# MXChip.net
KiCad netlist of a schematic drawn in Altium Designer
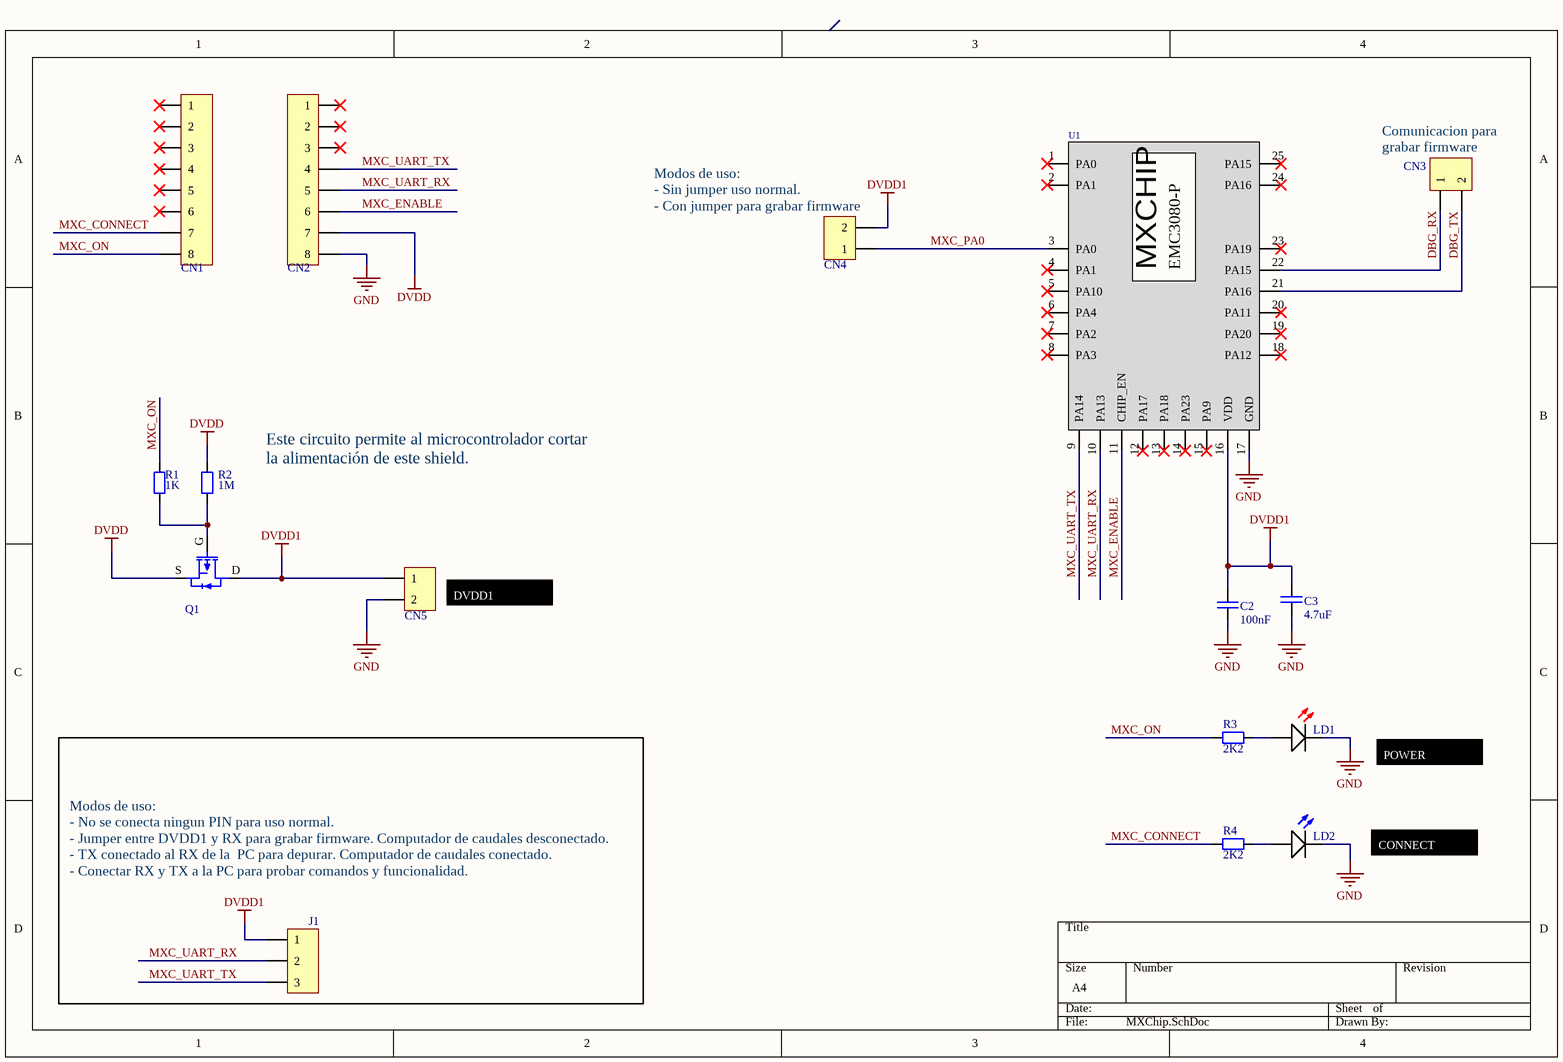
[diagram p0: MXChip.SchDoc]

(export (version "E")
  (design (tool "Eeschema 10.0.6"))
  (components
    (comp (ref "C2")
      (value "100nF")
      (footprint "CAP_SM0805_YAGEOCC2_N")
      (description "CAP 100nF SM0805 X7R 25V YAGEO CC2")
      (fields
        (field (name "MANUFACTURER") "Yageo")
        (field (name "MANUFACTURER PART NUMBER") "CC0805KRX7R8BB104")
      )
      (libsource (lib "Yageo") (part "CC0805KRX7R8BB104"))
    )
    (comp (ref "C3")
      (value "4.7uF")
      (footprint "CAP_SM0805_YAGEOCC2_N")
      (description "CAP 4.7uF SM0805 X5R 10V YAGEO CC2")
      (fields
        (field (name "MANUFACTURER") "Yageo")
        (field (name "MANUFACTURER PART NUMBER") "CC0805KRX5R6BB475")
      )
      (libsource (lib "Yageo") (part "CC0805KRX5R6BB475"))
    )
    (comp (ref "CN1")
      (value "DEALON DZ200R-11-08-39")
      (footprint "HEADER PIN 1X8 2mm")
      (description "1 x 8 - true hole  2mm - Pb free")
      (fields
        (field (name "MANUFACTURER") "Amphenol ICC")
        (field (name "MANUFACTURER PART NUMBER") "DZ200R-11-08-39")
      )
      (libsource (lib "header_pin") (part "DEALON DZ200R-11-08-39"))
    )
    (comp (ref "CN2")
      (value "DEALON DZ200R-11-08-39")
      (footprint "HEADER PIN 1X8 2mm")
      (description "1 x 8 - true hole  2mm - Pb free")
      (fields
        (field (name "MANUFACTURER") "Amphenol ICC")
        (field (name "MANUFACTURER PART NUMBER") "DZ200R-11-08-39")
      )
      (libsource (lib "") (part "DEALON DZ200R-11-08-39_1"))
    )
    (comp (ref "CN3")
      (value "Completar BOM con modelo 54101-T0600LF (o equivalente), es de 36 posiciones, este componente necesita cortar 2 por componente")
      (footprint "HEADER PIN 1X2")
      (description "1 x 2 - true hole  2.54mm - Pb free")
      (fields (field (name "MANUFACTURER") "Amphenol ICC"))
      (libsource (lib "") (part "54101-T0600LF-CUT-2_1"))
    )
    (comp (ref "CN4")
      (value "Completar BOM con modelo 54101-T0600LF (o equivalente), es de 36 posiciones, este componente necesita cortar 2 por componente")
      (footprint "HEADER PIN 1X2")
      (description "1 x 2 - true hole  2.54mm - Pb free")
      (fields (field (name "MANUFACTURER") "Amphenol ICC"))
      (libsource (lib "") (part "54101-T0600LF-CUT-2_2"))
    )
    (comp (ref "CN5")
      (value "Completar BOM con modelo 54101-T0600LF (o equivalente), es de 36 posiciones, este componente necesita cortar 2 por componente")
      (footprint "HEADER PIN 1X2")
      (description "1 x 2 - true hole  2.54mm - Pb free")
      (fields (field (name "MANUFACTURER") "Amphenol ICC"))
      (libsource (lib "header_pin") (part "54101-T0600LF-CUT-2"))
    )
    (comp (ref "J1")
      (value "Completar BOM con modelo 54101-T0600LF (o equivalente), es de 36 posiciones, este componente necesita cortar 3 por componente")
      (footprint "HEADER PIN 1X3")
      (description "1 x 3 - true hole  2.54mm - Pb free")
      (fields
        (field (name "MANUFACTURER") "Amphenol ICC")
        (field (name "MANUFACTURER PART NUMBER") "54101-T0600LF")
      )
      (libsource (lib "header_pin") (part "54101-T0600LF-CUT-3"))
    )
    (comp (ref "LD1")
      (value "ERROR")
      (footprint "LED 0805")
      (fields
        (field (name "MANUFACTURER") "Everlight Elec")
        (field (name "MANUFACTURER PART NUMBER") "17-21SURC/S530-A2/TR8")
      )
      (libsource (lib "LED") (part "17-21SURC/S530-A2/TR8"))
    )
    (comp (ref "LD2")
      (value "RUN")
      (footprint "LED 0805")
      (fields
        (field (name "MANUFACTURER") "Everlight Elec")
        (field (name "MANUFACTURER PART NUMBER") "17-21/BHC-XL2M2TY")
      )
      (libsource (lib "LED") (part "17-21/BHC-XL2M2TY/3T"))
    )
    (comp (ref "Q1")
      (value "DMG3401LSN-7")
      (footprint "DMG3401LSN-7")
      (description "P-CHANNEL ENHANCEMENT MODE MOSFET\r\nRDS(ON) = 85mΩ @ VGS = -2.5V -> ID -2.7A\r\nV(BR)DDS 30V")
      (fields (field (name "MANUFACTURER") "Diodes Incorporated"))
      (libsource (lib "mosfet") (part "DMG3401LSN-7"))
    )
    (comp (ref "R1")
      (value "1K")
      (footprint "RES_SM0805_YAGEORC_N")
      (description "RES 1K SM0805 YAGEO RC_L")
      (fields
        (field (name "MANUFACTURER") "Yageo")
        (field (name "MANUFACTURER PART NUMBER") "RC0805FR-071KL")
      )
      (libsource (lib "Yageo") (part "RC0805FR-071KL"))
    )
    (comp (ref "R2")
      (value "1M")
      (footprint "RES_SM0805_YAGEORC_N")
      (description "RES 1M SM0805 YAGEO RC_L")
      (fields
        (field (name "MANUFACTURER") "Yageo")
        (field (name "MANUFACTURER PART NUMBER") "RC0805FR-071ML")
      )
      (libsource (lib "Yageo") (part "RC0805FR-071ML"))
    )
    (comp (ref "R3")
      (value "2K2")
      (footprint "RES_SM0805_YAGEORC_N")
      (description "RES 2K2 SM0805 YAGEO RC_L")
      (fields
        (field (name "MANUFACTURER") "Yageo")
        (field (name "MANUFACTURER PART NUMBER") "RC0805FR-072K2L")
      )
      (libsource (lib "Yageo") (part "RC0805FR-072K2L"))
    )
    (comp (ref "R4")
      (value "2K2")
      (footprint "RES_SM0805_YAGEORC_N")
      (description "RES 2K2 SM0805 YAGEO RC_L")
      (fields
        (field (name "MANUFACTURER") "Yageo")
        (field (name "MANUFACTURER PART NUMBER") "RC0805FR-072K2L")
      )
      (libsource (lib "Yageo") (part "RC0805FR-072K2L"))
    )
    (comp (ref "U1")
      (value "EMC3080-P")
      (footprint "EMC3080-P")
      (description "Solamente es el zocalo donde va montado el chip, por eso no tiene modelo 3D")
      (fields (field (name "MANUFACTURER") "MXCHIP"))
      (libsource (lib "Microcontroladores") (part "EMC3080-P"))
    )
  )
  (nets
    (net (code "1") (name "/DBG_RX") (class "Default")
      (node (ref "CN3") (pin "1") (pinfunction "1_1") (pintype "passive"))
      (node (ref "U1") (pin "22") (pinfunction "PA15_22") (pintype "passive"))
    )
    (net (code "2") (name "/DBG_TX") (class "Default")
      (node (ref "CN3") (pin "2") (pinfunction "2_2") (pintype "passive"))
      (node (ref "U1") (pin "21") (pinfunction "PA16_21") (pintype "passive"))
    )
    (net (code "3") (name "/MXC_CONNECT") (class "Default")
      (node (ref "CN1") (pin "7") (pinfunction "7_7") (pintype "passive"))
      (node (ref "R4") (pin "1") (pintype "passive"))
    )
    (net (code "4") (name "/MXC_ENABLE") (class "Default")
      (node (ref "CN2") (pin "6") (pinfunction "6_6") (pintype "passive"))
      (node (ref "U1") (pin "11") (pinfunction "CHIP_EN_11") (pintype "passive"))
    )
    (net (code "5") (name "/MXC_ON") (class "Default")
      (node (ref "CN1") (pin "8") (pinfunction "8_8") (pintype "passive"))
      (node (ref "R1") (pin "2") (pintype "passive"))
      (node (ref "R3") (pin "1") (pintype "passive"))
    )
    (net (code "6") (name "/MXC_PA0") (class "Default")
      (node (ref "CN4") (pin "1") (pinfunction "1_1") (pintype "passive"))
      (node (ref "U1") (pin "3") (pinfunction "PA0_3") (pintype "passive"))
    )
    (net (code "7") (name "/MXC_UART_RX") (class "Default")
      (node (ref "CN2") (pin "5") (pinfunction "5_5") (pintype "passive"))
      (node (ref "J1") (pin "2") (pinfunction "2_2") (pintype "passive"))
      (node (ref "U1") (pin "10") (pinfunction "PA13_10") (pintype "passive"))
    )
    (net (code "8") (name "/MXC_UART_TX") (class "Default")
      (node (ref "CN2") (pin "4") (pinfunction "4_4") (pintype "passive"))
      (node (ref "J1") (pin "3") (pinfunction "3_3") (pintype "passive"))
      (node (ref "U1") (pin "9") (pinfunction "PA14_9") (pintype "passive"))
    )
    (net (code "9") (name "DVDD") (class "Default")
      (node (ref "CN2") (pin "7") (pinfunction "7_7") (pintype "passive"))
      (node (ref "Q1") (pin "S") (pinfunction "S_S") (pintype "passive"))
      (node (ref "R2") (pin "2") (pintype "passive"))
    )
    (net (code "10") (name "DVDD1") (class "Default")
      (node (ref "C2") (pin "1") (pintype "passive"))
      (node (ref "C3") (pin "1") (pintype "passive"))
      (node (ref "CN4") (pin "2") (pinfunction "2_2") (pintype "passive"))
      (node (ref "CN5") (pin "1") (pinfunction "1_1") (pintype "passive"))
      (node (ref "J1") (pin "1") (pinfunction "1_1") (pintype "passive"))
      (node (ref "Q1") (pin "D") (pinfunction "D_D") (pintype "passive"))
      (node (ref "U1") (pin "16") (pinfunction "VDD_16") (pintype "passive"))
    )
    (net (code "11") (name "GND") (class "Default")
      (node (ref "C2") (pin "2") (pintype "passive"))
      (node (ref "C3") (pin "2") (pintype "passive"))
      (node (ref "CN2") (pin "8") (pinfunction "8_8") (pintype "passive"))
      (node (ref "CN5") (pin "2") (pinfunction "2_2") (pintype "passive"))
      (node (ref "LD1") (pin "K") (pinfunction "K_K") (pintype "passive"))
      (node (ref "LD2") (pin "K") (pinfunction "K_K") (pintype "passive"))
      (node (ref "U1") (pin "17") (pinfunction "GND_17") (pintype "passive"))
    )
    (net (code "12") (name "Net-(LD1-PadA)") (class "Default")
      (node (ref "LD1") (pin "A") (pinfunction "A_A") (pintype "passive"))
      (node (ref "R3") (pin "2") (pintype "passive"))
    )
    (net (code "13") (name "Net-(LD2-PadA)") (class "Default")
      (node (ref "LD2") (pin "A") (pinfunction "A_A") (pintype "passive"))
      (node (ref "R4") (pin "2") (pintype "passive"))
    )
    (net (code "14") (name "Net-(Q1-PadG)") (class "Default")
      (node (ref "Q1") (pin "G") (pinfunction "G_G") (pintype "passive"))
      (node (ref "R1") (pin "1") (pintype "passive"))
      (node (ref "R2") (pin "1") (pintype "passive"))
    )
    (net (code "15") (name "unconnected-(CN1-Pad1)") (class "Default")
      (node (ref "CN1") (pin "1") (pinfunction "1_1") (pintype "passive+no_connect"))
    )
    (net (code "16") (name "unconnected-(CN1-Pad2)") (class "Default")
      (node (ref "CN1") (pin "2") (pinfunction "2_2") (pintype "passive+no_connect"))
    )
    (net (code "17") (name "unconnected-(CN1-Pad3)") (class "Default")
      (node (ref "CN1") (pin "3") (pinfunction "3_3") (pintype "passive+no_connect"))
    )
    (net (code "18") (name "unconnected-(CN1-Pad4)") (class "Default")
      (node (ref "CN1") (pin "4") (pinfunction "4_4") (pintype "passive+no_connect"))
    )
    (net (code "19") (name "unconnected-(CN1-Pad5)") (class "Default")
      (node (ref "CN1") (pin "5") (pinfunction "5_5") (pintype "passive+no_connect"))
    )
    (net (code "20") (name "unconnected-(CN1-Pad6)") (class "Default")
      (node (ref "CN1") (pin "6") (pinfunction "6_6") (pintype "passive+no_connect"))
    )
    (net (code "21") (name "unconnected-(CN2-Pad1)") (class "Default")
      (node (ref "CN2") (pin "1") (pinfunction "1_1") (pintype "passive+no_connect"))
    )
    (net (code "22") (name "unconnected-(CN2-Pad2)") (class "Default")
      (node (ref "CN2") (pin "2") (pinfunction "2_2") (pintype "passive+no_connect"))
    )
    (net (code "23") (name "unconnected-(CN2-Pad3)") (class "Default")
      (node (ref "CN2") (pin "3") (pinfunction "3_3") (pintype "passive+no_connect"))
    )
    (net (code "24") (name "unconnected-(U1-PA0-Pad1)") (class "Default")
      (node (ref "U1") (pin "1") (pinfunction "PA0_1") (pintype "passive+no_connect"))
    )
    (net (code "25") (name "unconnected-(U1-PA1-Pad2)") (class "Default")
      (node (ref "U1") (pin "2") (pinfunction "PA1_2") (pintype "passive+no_connect"))
    )
    (net (code "26") (name "unconnected-(U1-PA1-Pad4)") (class "Default")
      (node (ref "U1") (pin "4") (pinfunction "PA1_4") (pintype "passive+no_connect"))
    )
    (net (code "27") (name "unconnected-(U1-PA2-Pad7)") (class "Default")
      (node (ref "U1") (pin "7") (pinfunction "PA2_7") (pintype "passive+no_connect"))
    )
    (net (code "28") (name "unconnected-(U1-PA3-Pad8)") (class "Default")
      (node (ref "U1") (pin "8") (pinfunction "PA3_8") (pintype "passive+no_connect"))
    )
    (net (code "29") (name "unconnected-(U1-PA4-Pad6)") (class "Default")
      (node (ref "U1") (pin "6") (pinfunction "PA4_6") (pintype "passive+no_connect"))
    )
    (net (code "30") (name "unconnected-(U1-PA9-Pad15)") (class "Default")
      (node (ref "U1") (pin "15") (pinfunction "PA9_15") (pintype "passive+no_connect"))
    )
    (net (code "31") (name "unconnected-(U1-PA10-Pad5)") (class "Default")
      (node (ref "U1") (pin "5") (pinfunction "PA10_5") (pintype "passive+no_connect"))
    )
    (net (code "32") (name "unconnected-(U1-PA11-Pad20)") (class "Default")
      (node (ref "U1") (pin "20") (pinfunction "PA11_20") (pintype "passive+no_connect"))
    )
    (net (code "33") (name "unconnected-(U1-PA12-Pad18)") (class "Default")
      (node (ref "U1") (pin "18") (pinfunction "PA12_18") (pintype "passive+no_connect"))
    )
    (net (code "34") (name "unconnected-(U1-PA15-Pad25)") (class "Default")
      (node (ref "U1") (pin "25") (pinfunction "PA15_25") (pintype "passive+no_connect"))
    )
    (net (code "35") (name "unconnected-(U1-PA16-Pad24)") (class "Default")
      (node (ref "U1") (pin "24") (pinfunction "PA16_24") (pintype "passive+no_connect"))
    )
    (net (code "36") (name "unconnected-(U1-PA17-Pad12)") (class "Default")
      (node (ref "U1") (pin "12") (pinfunction "PA17_12") (pintype "passive+no_connect"))
    )
    (net (code "37") (name "unconnected-(U1-PA18-Pad13)") (class "Default")
      (node (ref "U1") (pin "13") (pinfunction "PA18_13") (pintype "passive+no_connect"))
    )
    (net (code "38") (name "unconnected-(U1-PA19-Pad23)") (class "Default")
      (node (ref "U1") (pin "23") (pinfunction "PA19_23") (pintype "passive+no_connect"))
    )
    (net (code "39") (name "unconnected-(U1-PA20-Pad19)") (class "Default")
      (node (ref "U1") (pin "19") (pinfunction "PA20_19") (pintype "passive+no_connect"))
    )
    (net (code "40") (name "unconnected-(U1-PA23-Pad14)") (class "Default")
      (node (ref "U1") (pin "14") (pinfunction "PA23_14") (pintype "passive+no_connect"))
    )
  )
)
